# Schematic.net
KiCad netlist of a schematic drawn in Altium Designer
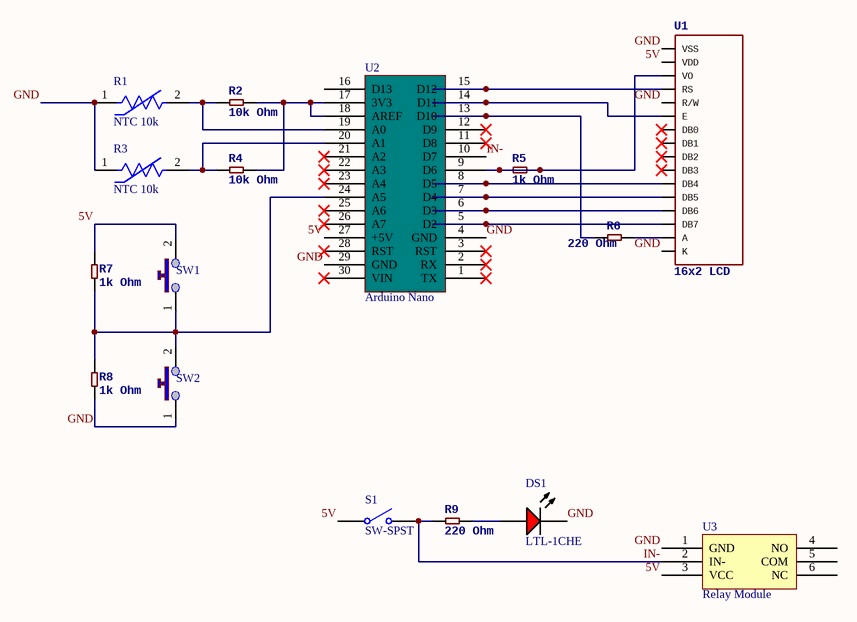
[diagram p0: Schematic.SchDoc]

(export (version "E")
  (design (tool "Eeschema 10.0.6"))
  (components
    (comp (ref "DS1")
      (value "LTL-1CHE")
      (footprint "INDPR60-254-520X380X650")
      (description "LED Uni-Color Red, 100 mW, 30 mA, -55 to 100 degC, 2-Pin THD, RoHS, Bulk")
      (fields (field (name "MANUFACTURER") "Lite-On"))
      (libsource (lib "Blagojce Kolicoski") (part "LED-RED-AK-2"))
    )
    (comp (ref "R1")
      (value "NTC 10k")
      (footprint "FP-NTCLE305E4103SB-MFG")
      (description "THERMISTOR NTC 10KOHM 3984K BEAD")
      (fields (field (name "TOLERANCE") "2.2%"))
      (libsource (lib "Altium Content Vault") (part "3b148a6ebabc5fb4d708a66c052d352"))
    )
    (comp (ref "R2")
      (value "10k Ohm")
      (footprint "Res 1/4w")
      (libsource (lib "AltiumLibraryDDT") (part "RES_THT"))
    )
    (comp (ref "R3")
      (value "NTC 10k")
      (footprint "FP-NTCLE305E4103SB-MFG")
      (description "THERMISTOR NTC 10KOHM 3984K BEAD")
      (fields (field (name "TOLERANCE") "2.2%"))
      (libsource (lib "Altium Content Vault") (part "3b148a6ebabc5fb4d708a66c052d352"))
    )
    (comp (ref "R4")
      (value "10k Ohm")
      (footprint "Res 1/4w")
      (libsource (lib "AltiumLibraryDDT") (part "RES_THT"))
    )
    (comp (ref "R5")
      (value "1k Ohm")
      (footprint "Res 1/4w")
      (libsource (lib "AltiumLibraryDDT") (part "RES_THT"))
    )
    (comp (ref "R6")
      (value "220 Ohm")
      (footprint "Res 1/4w")
      (libsource (lib "AltiumLibraryDDT") (part "RES_THT"))
    )
    (comp (ref "R7")
      (value "1k Ohm")
      (footprint "Res 1/4w")
      (libsource (lib "AltiumLibraryDDT") (part "RES_THT"))
    )
    (comp (ref "R8")
      (value "1k Ohm")
      (footprint "Res 1/4w")
      (libsource (lib "AltiumLibraryDDT") (part "RES_THT"))
    )
    (comp (ref "R9")
      (value "220 Ohm")
      (footprint "Res 1/4w")
      (libsource (lib "AltiumLibraryDDT") (part "RES_THT"))
    )
    (comp (ref "S1")
      (value "SW-SPST")
      (footprint "SPST-2")
      (description "Single-Pole, Single-Throw Switch")
      (fields (field (name "PUBLISHER") "Altium Limited"))
      (libsource (lib "Miscellaneous Devices") (part "SW-SPST"))
    )
    (comp (ref "SW1")
      (value "~")
      (footprint "2 Pin Solder Cable")
      (libsource (lib "Schlib1") (part "Push Button"))
    )
    (comp (ref "SW2")
      (value "~")
      (footprint "2 Pin Solder Cable")
      (libsource (lib "Schlib1") (part "Push Button"))
    )
    (comp (ref "U1")
      (value "16x2 LCD")
      (footprint "LCD-16X2")
      (libsource (lib "AltiumLibraryDDT") (part "LCD-16X2SILK"))
    )
    (comp (ref "U2")
      (value "Arduino Nano")
      (footprint "PCB:PCBComponent_1")
      (libsource (lib "Nano") (part "Component_1"))
    )
    (comp (ref "U3")
      (value "Relay Module")
      (footprint "RelayModule")
      (libsource (lib "Schlib1") (part "Relay Module"))
    )
  )
  (nets
    (net (code "1") (name "/5V") (class "Default")
      (node (ref "R7") (pin "2") (pinfunction "2_2") (pintype "passive"))
      (node (ref "S1") (pin "1") (pinfunction "COMMON_1") (pintype "passive"))
      (node (ref "SW1") (pin "2") (pintype "passive"))
      (node (ref "U1") (pin "2") (pinfunction "VDD_2") (pintype "power_in"))
      (node (ref "U2") (pin "27") (pinfunction "+5V_27") (pintype "passive"))
      (node (ref "U3") (pin "3") (pinfunction "VCC_3") (pintype "passive"))
    )
    (net (code "2") (name "/GND") (class "Default")
      (node (ref "DS1") (pin "2") (pinfunction "K_2") (pintype "passive"))
      (node (ref "R1") (pin "1") (pinfunction "1_1") (pintype "passive"))
      (node (ref "R3") (pin "1") (pinfunction "1_1") (pintype "passive"))
      (node (ref "R8") (pin "1") (pinfunction "1_1") (pintype "passive"))
      (node (ref "SW2") (pin "1") (pintype "passive"))
      (node (ref "U1") (pin "1") (pinfunction "VSS_1") (pintype "power_in"))
      (node (ref "U1") (pin "16") (pinfunction "K_16") (pintype "power_in"))
      (node (ref "U1") (pin "5") (pinfunction "R/W_5") (pintype "passive"))
      (node (ref "U2") (pin "29") (pinfunction "GND_29") (pintype "passive"))
      (node (ref "U2") (pin "4") (pinfunction "GND_4") (pintype "passive"))
      (node (ref "U3") (pin "1") (pinfunction "GND_1") (pintype "passive"))
    )
    (net (code "3") (name "/IN-") (class "Default")
      (node (ref "R9") (pin "1") (pinfunction "1_1") (pintype "passive"))
      (node (ref "S1") (pin "2") (pinfunction "NO_2") (pintype "passive"))
      (node (ref "U2") (pin "10") (pinfunction "D7_10") (pintype "passive"))
      (node (ref "U3") (pin "2") (pinfunction "IN-_2") (pintype "passive"))
    )
    (net (code "4") (name "Net-(DS1-A)") (class "Default")
      (node (ref "DS1") (pin "1") (pinfunction "A_1") (pintype "passive"))
      (node (ref "R9") (pin "2") (pinfunction "2_2") (pintype "passive"))
    )
    (net (code "5") (name "Net-(U1-A)") (class "Default")
      (node (ref "R6") (pin "2") (pinfunction "2_2") (pintype "passive"))
      (node (ref "U1") (pin "15") (pinfunction "A_15") (pintype "power_in"))
    )
    (net (code "6") (name "Net-(U1-DB4)") (class "Default")
      (node (ref "U1") (pin "11") (pinfunction "DB4_11") (pintype "passive"))
      (node (ref "U2") (pin "8") (pinfunction "D5_8") (pintype "passive"))
    )
    (net (code "7") (name "Net-(U1-DB5)") (class "Default")
      (node (ref "U1") (pin "12") (pinfunction "DB5_12") (pintype "passive"))
      (node (ref "U2") (pin "7") (pinfunction "D4_7") (pintype "passive"))
    )
    (net (code "8") (name "Net-(U1-DB6)") (class "Default")
      (node (ref "U1") (pin "13") (pinfunction "DB6_13") (pintype "passive"))
      (node (ref "U2") (pin "6") (pinfunction "D3_6") (pintype "passive"))
    )
    (net (code "9") (name "Net-(U1-DB7)") (class "Default")
      (node (ref "U1") (pin "14") (pinfunction "DB7_14") (pintype "passive"))
      (node (ref "U2") (pin "5") (pinfunction "D2_5") (pintype "passive"))
    )
    (net (code "10") (name "Net-(U1-E)") (class "Default")
      (node (ref "U1") (pin "6") (pinfunction "E_6") (pintype "passive"))
      (node (ref "U2") (pin "14") (pinfunction "D11_14") (pintype "passive"))
    )
    (net (code "11") (name "Net-(U1-RS)") (class "Default")
      (node (ref "U1") (pin "4") (pinfunction "RS_4") (pintype "passive"))
      (node (ref "U2") (pin "15") (pinfunction "D12_15") (pintype "passive"))
    )
    (net (code "12") (name "Net-(U1-VO)") (class "Default")
      (node (ref "R5") (pin "1") (pinfunction "1_1") (pintype "passive"))
      (node (ref "R5") (pin "2") (pinfunction "2_2") (pintype "passive"))
      (node (ref "U1") (pin "3") (pinfunction "VO_3") (pintype "passive"))
      (node (ref "U2") (pin "9") (pinfunction "D6_9") (pintype "passive"))
    )
    (net (code "13") (name "Net-(U2-3V3)") (class "Default")
      (node (ref "R2") (pin "2") (pinfunction "2_2") (pintype "passive"))
      (node (ref "R4") (pin "2") (pinfunction "2_2") (pintype "passive"))
      (node (ref "U2") (pin "17") (pinfunction "3V3_17") (pintype "passive"))
      (node (ref "U2") (pin "18") (pinfunction "AREF_18") (pintype "passive"))
    )
    (net (code "14") (name "Net-(U2-A0)") (class "Default")
      (node (ref "R1") (pin "2") (pinfunction "2_2") (pintype "passive"))
      (node (ref "R2") (pin "1") (pinfunction "1_1") (pintype "passive"))
      (node (ref "U2") (pin "19") (pinfunction "A0_19") (pintype "passive"))
    )
    (net (code "15") (name "Net-(U2-A1)") (class "Default")
      (node (ref "R3") (pin "2") (pinfunction "2_2") (pintype "passive"))
      (node (ref "R4") (pin "1") (pinfunction "1_1") (pintype "passive"))
      (node (ref "U2") (pin "20") (pinfunction "A1_20") (pintype "passive"))
    )
    (net (code "16") (name "Net-(U2-A5)") (class "Default")
      (node (ref "R7") (pin "1") (pinfunction "1_1") (pintype "passive"))
      (node (ref "R8") (pin "2") (pinfunction "2_2") (pintype "passive"))
      (node (ref "SW1") (pin "1") (pintype "passive"))
      (node (ref "SW2") (pin "2") (pintype "passive"))
      (node (ref "U2") (pin "24") (pinfunction "A5_24") (pintype "passive"))
    )
    (net (code "17") (name "Net-(U2-D10)") (class "Default")
      (node (ref "R6") (pin "1") (pinfunction "1_1") (pintype "passive"))
      (node (ref "U2") (pin "13") (pinfunction "D10_13") (pintype "passive"))
    )
    (net (code "18") (name "unconnected-(U1-DB0-Pad7)") (class "Default")
      (node (ref "U1") (pin "7") (pinfunction "DB0_7") (pintype "passive+no_connect"))
    )
    (net (code "19") (name "unconnected-(U1-DB1-Pad8)") (class "Default")
      (node (ref "U1") (pin "8") (pinfunction "DB1_8") (pintype "passive+no_connect"))
    )
    (net (code "20") (name "unconnected-(U1-DB2-Pad9)") (class "Default")
      (node (ref "U1") (pin "9") (pinfunction "DB2_9") (pintype "passive+no_connect"))
    )
    (net (code "21") (name "unconnected-(U1-DB3-Pad10)") (class "Default")
      (node (ref "U1") (pin "10") (pinfunction "DB3_10") (pintype "passive+no_connect"))
    )
    (net (code "22") (name "unconnected-(U2-A2-Pad21)") (class "Default")
      (node (ref "U2") (pin "21") (pinfunction "A2_21") (pintype "passive+no_connect"))
    )
    (net (code "23") (name "unconnected-(U2-A3-Pad22)") (class "Default")
      (node (ref "U2") (pin "22") (pinfunction "A3_22") (pintype "passive+no_connect"))
    )
    (net (code "24") (name "unconnected-(U2-A4-Pad23)") (class "Default")
      (node (ref "U2") (pin "23") (pinfunction "A4_23") (pintype "passive+no_connect"))
    )
    (net (code "25") (name "unconnected-(U2-A6-Pad25)") (class "Default")
      (node (ref "U2") (pin "25") (pinfunction "A6_25") (pintype "passive+no_connect"))
    )
    (net (code "26") (name "unconnected-(U2-A7-Pad26)") (class "Default")
      (node (ref "U2") (pin "26") (pinfunction "A7_26") (pintype "passive+no_connect"))
    )
    (net (code "27") (name "unconnected-(U2-D8-Pad11)") (class "Default")
      (node (ref "U2") (pin "11") (pinfunction "D8_11") (pintype "passive+no_connect"))
    )
    (net (code "28") (name "unconnected-(U2-D9-Pad12)") (class "Default")
      (node (ref "U2") (pin "12") (pinfunction "D9_12") (pintype "passive+no_connect"))
    )
    (net (code "29") (name "unconnected-(U2-D13-Pad16)") (class "Default")
      (node (ref "U2") (pin "16") (pinfunction "D13_16") (pintype "passive"))
    )
    (net (code "30") (name "unconnected-(U2-RST-Pad3)") (class "Default")
      (node (ref "U2") (pin "3") (pinfunction "RST_3") (pintype "passive+no_connect"))
    )
    (net (code "31") (name "unconnected-(U2-RST-Pad28)") (class "Default")
      (node (ref "U2") (pin "28") (pinfunction "RST_28") (pintype "passive+no_connect"))
    )
    (net (code "32") (name "unconnected-(U2-RX-Pad2)") (class "Default")
      (node (ref "U2") (pin "2") (pinfunction "RX_2") (pintype "passive+no_connect"))
    )
    (net (code "33") (name "unconnected-(U2-TX-Pad1)") (class "Default")
      (node (ref "U2") (pin "1") (pinfunction "TX_1") (pintype "passive+no_connect"))
    )
    (net (code "34") (name "unconnected-(U2-VIN-Pad30)") (class "Default")
      (node (ref "U2") (pin "30") (pinfunction "VIN_30") (pintype "passive+no_connect"))
    )
    (net (code "35") (name "unconnected-(U3-COM-Pad5)") (class "Default")
      (node (ref "U3") (pin "5") (pinfunction "COM_5") (pintype "passive"))
    )
    (net (code "36") (name "unconnected-(U3-NC-Pad6)") (class "Default")
      (node (ref "U3") (pin "6") (pinfunction "NC_6") (pintype "passive"))
    )
    (net (code "37") (name "unconnected-(U3-NO-Pad4)") (class "Default")
      (node (ref "U3") (pin "4") (pinfunction "NO_4") (pintype "passive"))
    )
  )
)
